# M900D.net
KiCad netlist of a schematic drawn in EAGLE
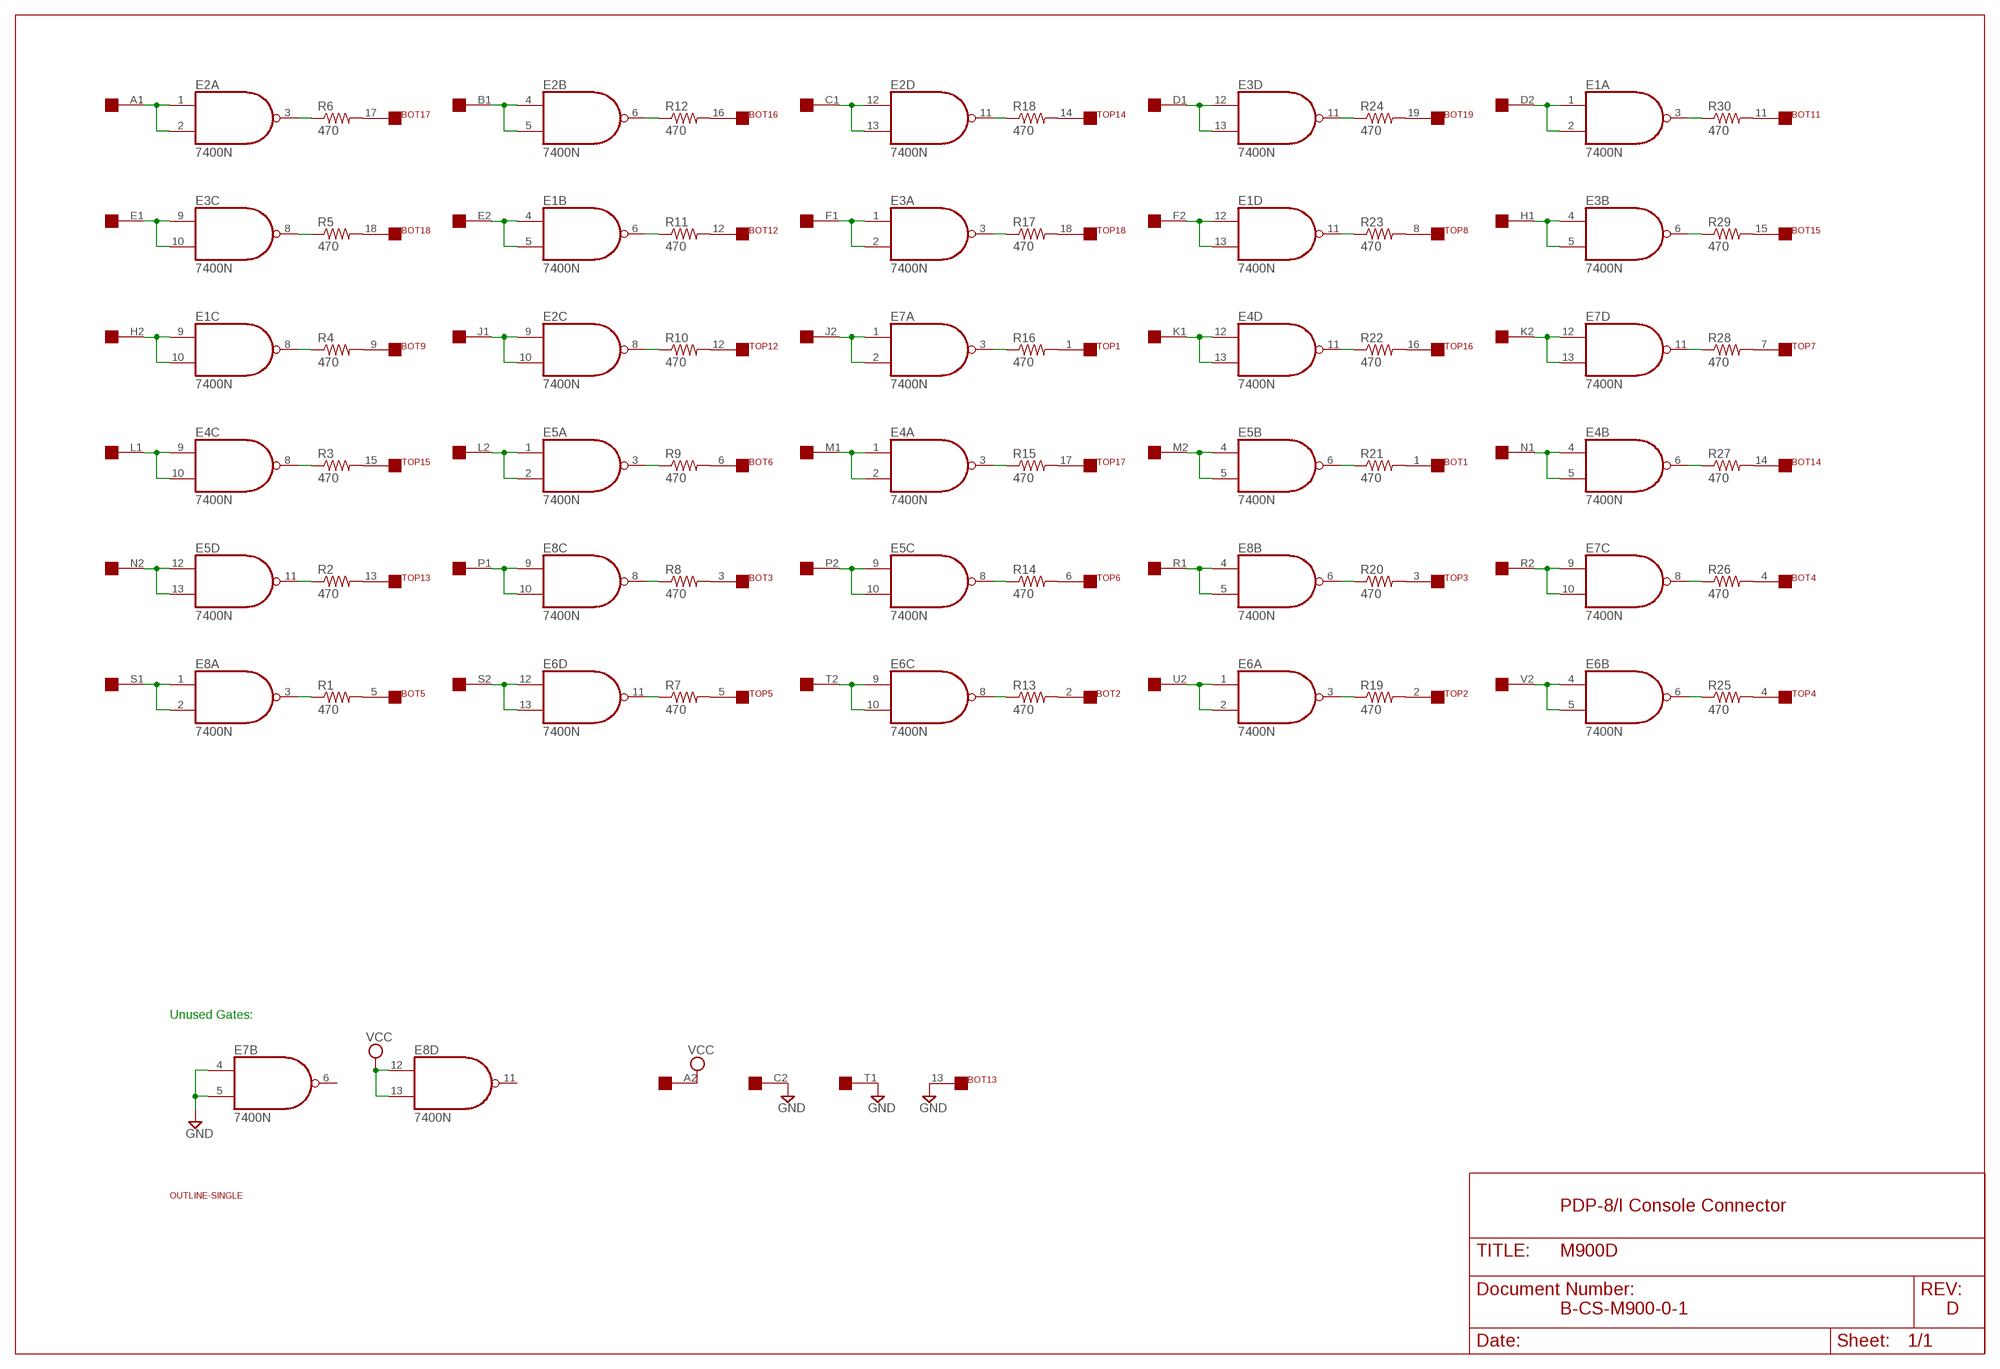
[diagram p0: schematic, sheet 1]

(export (version "E")
  (design (tool "Eeschema 10.0.6"))
  (components
    (comp (ref "BOT")
      (value "FLEX19")
      (footprint "eagle-import:FLEX19")
      (libsource (lib "eagle-import") (part "FLEX19"))
    )
    (comp (ref "E1")
      (value "7400N")
      (footprint "eagle-import:DIL14")
      (libsource (lib "eagle-import") (part "7400N"))
    )
    (comp (ref "E2")
      (value "7400N")
      (footprint "eagle-import:DIL14")
      (libsource (lib "eagle-import") (part "7400N"))
    )
    (comp (ref "E3")
      (value "7400N")
      (footprint "eagle-import:DIL14")
      (libsource (lib "eagle-import") (part "7400N"))
    )
    (comp (ref "E4")
      (value "7400N")
      (footprint "eagle-import:DIL14")
      (libsource (lib "eagle-import") (part "7400N"))
    )
    (comp (ref "E5")
      (value "7400N")
      (footprint "eagle-import:DIL14")
      (libsource (lib "eagle-import") (part "7400N"))
    )
    (comp (ref "E6")
      (value "7400N")
      (footprint "eagle-import:DIL14")
      (libsource (lib "eagle-import") (part "7400N"))
    )
    (comp (ref "E7")
      (value "7400N")
      (footprint "eagle-import:DIL14")
      (libsource (lib "eagle-import") (part "7400N"))
    )
    (comp (ref "E8")
      (value "7400N")
      (footprint "eagle-import:DIL14")
      (libsource (lib "eagle-import") (part "7400N"))
    )
    (comp (ref "EDGE")
      (value "SINGLE")
      (footprint "eagle-import:EDGE-CON2")
      (libsource (lib "eagle-import") (part "SINGLE"))
    )
    (comp (ref "R1")
      (value "470")
      (footprint "eagle-import:0207_10")
      (libsource (lib "eagle-import") (part "R-US_0207/10"))
    )
    (comp (ref "R2")
      (value "470")
      (footprint "eagle-import:0207_10")
      (libsource (lib "eagle-import") (part "R-US_0207/10"))
    )
    (comp (ref "R3")
      (value "470")
      (footprint "eagle-import:0207_10")
      (libsource (lib "eagle-import") (part "R-US_0207/10"))
    )
    (comp (ref "R4")
      (value "470")
      (footprint "eagle-import:0207_10")
      (libsource (lib "eagle-import") (part "R-US_0207/10"))
    )
    (comp (ref "R5")
      (value "470")
      (footprint "eagle-import:0207_10")
      (libsource (lib "eagle-import") (part "R-US_0207/10"))
    )
    (comp (ref "R6")
      (value "470")
      (footprint "eagle-import:0207_10")
      (libsource (lib "eagle-import") (part "R-US_0207/10"))
    )
    (comp (ref "R7")
      (value "470")
      (footprint "eagle-import:0207_10")
      (libsource (lib "eagle-import") (part "R-US_0207/10"))
    )
    (comp (ref "R8")
      (value "470")
      (footprint "eagle-import:0207_10")
      (libsource (lib "eagle-import") (part "R-US_0207/10"))
    )
    (comp (ref "R9")
      (value "470")
      (footprint "eagle-import:0207_10")
      (libsource (lib "eagle-import") (part "R-US_0207/10"))
    )
    (comp (ref "R10")
      (value "470")
      (footprint "eagle-import:0207_10")
      (libsource (lib "eagle-import") (part "R-US_0207/10"))
    )
    (comp (ref "R11")
      (value "470")
      (footprint "eagle-import:0207_10")
      (libsource (lib "eagle-import") (part "R-US_0207/10"))
    )
    (comp (ref "R12")
      (value "470")
      (footprint "eagle-import:0207_10")
      (libsource (lib "eagle-import") (part "R-US_0207/10"))
    )
    (comp (ref "R13")
      (value "470")
      (footprint "eagle-import:0207_10")
      (libsource (lib "eagle-import") (part "R-US_0207/10"))
    )
    (comp (ref "R14")
      (value "470")
      (footprint "eagle-import:0207_10")
      (libsource (lib "eagle-import") (part "R-US_0207/10"))
    )
    (comp (ref "R15")
      (value "470")
      (footprint "eagle-import:0207_10")
      (libsource (lib "eagle-import") (part "R-US_0207/10"))
    )
    (comp (ref "R16")
      (value "470")
      (footprint "eagle-import:0207_10")
      (libsource (lib "eagle-import") (part "R-US_0207/10"))
    )
    (comp (ref "R17")
      (value "470")
      (footprint "eagle-import:0207_10")
      (libsource (lib "eagle-import") (part "R-US_0207/10"))
    )
    (comp (ref "R18")
      (value "470")
      (footprint "eagle-import:0207_10")
      (libsource (lib "eagle-import") (part "R-US_0207/10"))
    )
    (comp (ref "R19")
      (value "470")
      (footprint "eagle-import:0207_10")
      (libsource (lib "eagle-import") (part "R-US_0207/10"))
    )
    (comp (ref "R20")
      (value "470")
      (footprint "eagle-import:0207_10")
      (libsource (lib "eagle-import") (part "R-US_0207/10"))
    )
    (comp (ref "R21")
      (value "470")
      (footprint "eagle-import:0207_10")
      (libsource (lib "eagle-import") (part "R-US_0207/10"))
    )
    (comp (ref "R22")
      (value "470")
      (footprint "eagle-import:0207_10")
      (libsource (lib "eagle-import") (part "R-US_0207/10"))
    )
    (comp (ref "R23")
      (value "470")
      (footprint "eagle-import:0207_10")
      (libsource (lib "eagle-import") (part "R-US_0207/10"))
    )
    (comp (ref "R24")
      (value "470")
      (footprint "eagle-import:0207_10")
      (libsource (lib "eagle-import") (part "R-US_0207/10"))
    )
    (comp (ref "R25")
      (value "470")
      (footprint "eagle-import:0207_10")
      (libsource (lib "eagle-import") (part "R-US_0207/10"))
    )
    (comp (ref "R26")
      (value "470")
      (footprint "eagle-import:0207_10")
      (libsource (lib "eagle-import") (part "R-US_0207/10"))
    )
    (comp (ref "R27")
      (value "470")
      (footprint "eagle-import:0207_10")
      (libsource (lib "eagle-import") (part "R-US_0207/10"))
    )
    (comp (ref "R28")
      (value "470")
      (footprint "eagle-import:0207_10")
      (libsource (lib "eagle-import") (part "R-US_0207/10"))
    )
    (comp (ref "R29")
      (value "470")
      (footprint "eagle-import:0207_10")
      (libsource (lib "eagle-import") (part "R-US_0207/10"))
    )
    (comp (ref "R30")
      (value "470")
      (footprint "eagle-import:0207_10")
      (libsource (lib "eagle-import") (part "R-US_0207/10"))
    )
    (comp (ref "TOP")
      (value "FLEX19")
      (footprint "eagle-import:FLEX19")
      (libsource (lib "eagle-import") (part "FLEX19"))
    )
    (comp (ref "U$2")
      (value "OUTLINE-SINGLE")
      (footprint "eagle-import:SINGLE")
      (libsource (lib "eagle-import") (part "OUTLINE-SINGLE"))
    )
  )
  (nets
    (net (code "1") (name "GND") (class "Default")
      (node (ref "BOT") (pin "13") (pinfunction "1_13") (pintype "passive"))
      (node (ref "E7") (pin "4") (pinfunction "I0_4") (pintype "input"))
      (node (ref "E7") (pin "5") (pinfunction "I1_5") (pintype "input"))
      (node (ref "EDGE") (pin "C2") (pinfunction "1_C2") (pintype "bidirectional"))
      (node (ref "EDGE") (pin "T1") (pinfunction "1_T1") (pintype "bidirectional"))
    )
    (net (code "2") (name "Net-(BOT-Pad1)") (class "Default")
      (node (ref "BOT") (pin "1") (pinfunction "1_1") (pintype "passive"))
      (node (ref "R21") (pin "2") (pinfunction "2_2") (pintype "passive"))
    )
    (net (code "3") (name "Net-(BOTC-1)") (class "Default")
      (node (ref "BOT") (pin "11") (pinfunction "1_11") (pintype "passive"))
      (node (ref "R30") (pin "2") (pinfunction "2_2") (pintype "passive"))
    )
    (net (code "4") (name "Net-(BOTD-1)") (class "Default")
      (node (ref "BOT") (pin "12") (pinfunction "1_12") (pintype "passive"))
      (node (ref "R11") (pin "2") (pinfunction "2_2") (pintype "passive"))
    )
    (net (code "5") (name "Net-(BOTF-1)") (class "Default")
      (node (ref "BOT") (pin "14") (pinfunction "1_14") (pintype "passive"))
      (node (ref "R27") (pin "2") (pinfunction "2_2") (pintype "passive"))
    )
    (net (code "6") (name "Net-(BOTG-1)") (class "Default")
      (node (ref "BOT") (pin "15") (pinfunction "1_15") (pintype "passive"))
      (node (ref "R29") (pin "2") (pinfunction "2_2") (pintype "passive"))
    )
    (net (code "7") (name "Net-(BOTH-1)") (class "Default")
      (node (ref "BOT") (pin "16") (pinfunction "1_16") (pintype "passive"))
      (node (ref "R12") (pin "2") (pinfunction "2_2") (pintype "passive"))
    )
    (net (code "8") (name "Net-(BOTI-1)") (class "Default")
      (node (ref "BOT") (pin "17") (pinfunction "1_17") (pintype "passive"))
      (node (ref "R6") (pin "2") (pinfunction "2_2") (pintype "passive"))
    )
    (net (code "9") (name "Net-(BOTJ-1)") (class "Default")
      (node (ref "BOT") (pin "18") (pinfunction "1_18") (pintype "passive"))
      (node (ref "R5") (pin "2") (pinfunction "2_2") (pintype "passive"))
    )
    (net (code "10") (name "Net-(BOTK-1)") (class "Default")
      (node (ref "BOT") (pin "19") (pinfunction "1_19") (pintype "passive"))
      (node (ref "R24") (pin "2") (pinfunction "2_2") (pintype "passive"))
    )
    (net (code "11") (name "Net-(BOTL-1)") (class "Default")
      (node (ref "BOT") (pin "2") (pinfunction "1_2") (pintype "passive"))
      (node (ref "R13") (pin "2") (pinfunction "2_2") (pintype "passive"))
    )
    (net (code "12") (name "Net-(BOTM-1)") (class "Default")
      (node (ref "BOT") (pin "3") (pinfunction "1_3") (pintype "passive"))
      (node (ref "R8") (pin "2") (pinfunction "2_2") (pintype "passive"))
    )
    (net (code "13") (name "Net-(BOTN-1)") (class "Default")
      (node (ref "BOT") (pin "4") (pinfunction "1_4") (pintype "passive"))
      (node (ref "R26") (pin "2") (pinfunction "2_2") (pintype "passive"))
    )
    (net (code "14") (name "Net-(BOTO-1)") (class "Default")
      (node (ref "BOT") (pin "5") (pinfunction "1_5") (pintype "passive"))
      (node (ref "R1") (pin "2") (pinfunction "2_2") (pintype "passive"))
    )
    (net (code "15") (name "Net-(BOTP-1)") (class "Default")
      (node (ref "BOT") (pin "6") (pinfunction "1_6") (pintype "passive"))
      (node (ref "R9") (pin "2") (pinfunction "2_2") (pintype "passive"))
    )
    (net (code "16") (name "Net-(BOTS-1)") (class "Default")
      (node (ref "BOT") (pin "9") (pinfunction "1_9") (pintype "passive"))
      (node (ref "R4") (pin "2") (pinfunction "2_2") (pintype "passive"))
    )
    (net (code "17") (name "Net-(E1A-I0)") (class "Default")
      (node (ref "E1") (pin "1") (pinfunction "I0_1") (pintype "input"))
      (node (ref "E1") (pin "2") (pinfunction "I1_2") (pintype "input"))
      (node (ref "EDGE") (pin "D2") (pinfunction "1_D2") (pintype "bidirectional"))
    )
    (net (code "18") (name "Net-(E1A-O)") (class "Default")
      (node (ref "E1") (pin "3") (pinfunction "O_3") (pintype "output"))
      (node (ref "R30") (pin "1") (pinfunction "1_1") (pintype "passive"))
    )
    (net (code "19") (name "Net-(E1B-I0)") (class "Default")
      (node (ref "E1") (pin "4") (pinfunction "I0_4") (pintype "input"))
      (node (ref "E1") (pin "5") (pinfunction "I1_5") (pintype "input"))
      (node (ref "EDGE") (pin "E2") (pinfunction "1_E2") (pintype "bidirectional"))
    )
    (net (code "20") (name "Net-(E1B-O)") (class "Default")
      (node (ref "E1") (pin "6") (pinfunction "O_6") (pintype "output"))
      (node (ref "R11") (pin "1") (pinfunction "1_1") (pintype "passive"))
    )
    (net (code "21") (name "Net-(E1C-I0)") (class "Default")
      (node (ref "E1") (pin "10") (pinfunction "I1_10") (pintype "input"))
      (node (ref "E1") (pin "9") (pinfunction "I0_9") (pintype "input"))
      (node (ref "EDGE") (pin "H2") (pinfunction "1_H2") (pintype "bidirectional"))
    )
    (net (code "22") (name "Net-(E1C-O)") (class "Default")
      (node (ref "E1") (pin "8") (pinfunction "O_8") (pintype "output"))
      (node (ref "R4") (pin "1") (pinfunction "1_1") (pintype "passive"))
    )
    (net (code "23") (name "Net-(E1D-I0)") (class "Default")
      (node (ref "E1") (pin "12") (pinfunction "I0_12") (pintype "input"))
      (node (ref "E1") (pin "13") (pinfunction "I1_13") (pintype "input"))
      (node (ref "EDGE") (pin "F2") (pinfunction "1_F2") (pintype "bidirectional"))
    )
    (net (code "24") (name "Net-(E1D-O)") (class "Default")
      (node (ref "E1") (pin "11") (pinfunction "O_11") (pintype "output"))
      (node (ref "R23") (pin "1") (pinfunction "1_1") (pintype "passive"))
    )
    (net (code "25") (name "Net-(E2A-I0)") (class "Default")
      (node (ref "E2") (pin "1") (pinfunction "I0_1") (pintype "input"))
      (node (ref "E2") (pin "2") (pinfunction "I1_2") (pintype "input"))
      (node (ref "EDGE") (pin "A1") (pinfunction "1_A1") (pintype "bidirectional"))
    )
    (net (code "26") (name "Net-(E2A-O)") (class "Default")
      (node (ref "E2") (pin "3") (pinfunction "O_3") (pintype "output"))
      (node (ref "R6") (pin "1") (pinfunction "1_1") (pintype "passive"))
    )
    (net (code "27") (name "Net-(E2B-I0)") (class "Default")
      (node (ref "E2") (pin "4") (pinfunction "I0_4") (pintype "input"))
      (node (ref "E2") (pin "5") (pinfunction "I1_5") (pintype "input"))
      (node (ref "EDGE") (pin "B1") (pinfunction "1_B1") (pintype "bidirectional"))
    )
    (net (code "28") (name "Net-(E2B-O)") (class "Default")
      (node (ref "E2") (pin "6") (pinfunction "O_6") (pintype "output"))
      (node (ref "R12") (pin "1") (pinfunction "1_1") (pintype "passive"))
    )
    (net (code "29") (name "Net-(E2C-I0)") (class "Default")
      (node (ref "E2") (pin "10") (pinfunction "I1_10") (pintype "input"))
      (node (ref "E2") (pin "9") (pinfunction "I0_9") (pintype "input"))
      (node (ref "EDGE") (pin "J1") (pinfunction "1_J1") (pintype "bidirectional"))
    )
    (net (code "30") (name "Net-(E2C-O)") (class "Default")
      (node (ref "E2") (pin "8") (pinfunction "O_8") (pintype "output"))
      (node (ref "R10") (pin "1") (pinfunction "1_1") (pintype "passive"))
    )
    (net (code "31") (name "Net-(E2D-I0)") (class "Default")
      (node (ref "E2") (pin "12") (pinfunction "I0_12") (pintype "input"))
      (node (ref "E2") (pin "13") (pinfunction "I1_13") (pintype "input"))
      (node (ref "EDGE") (pin "C1") (pinfunction "1_C1") (pintype "bidirectional"))
    )
    (net (code "32") (name "Net-(E2D-O)") (class "Default")
      (node (ref "E2") (pin "11") (pinfunction "O_11") (pintype "output"))
      (node (ref "R18") (pin "1") (pinfunction "1_1") (pintype "passive"))
    )
    (net (code "33") (name "Net-(E3A-I0)") (class "Default")
      (node (ref "E3") (pin "1") (pinfunction "I0_1") (pintype "input"))
      (node (ref "E3") (pin "2") (pinfunction "I1_2") (pintype "input"))
      (node (ref "EDGE") (pin "F1") (pinfunction "1_F1") (pintype "bidirectional"))
    )
    (net (code "34") (name "Net-(E3A-O)") (class "Default")
      (node (ref "E3") (pin "3") (pinfunction "O_3") (pintype "output"))
      (node (ref "R17") (pin "1") (pinfunction "1_1") (pintype "passive"))
    )
    (net (code "35") (name "Net-(E3B-I0)") (class "Default")
      (node (ref "E3") (pin "4") (pinfunction "I0_4") (pintype "input"))
      (node (ref "E3") (pin "5") (pinfunction "I1_5") (pintype "input"))
      (node (ref "EDGE") (pin "H1") (pinfunction "1_H1") (pintype "bidirectional"))
    )
    (net (code "36") (name "Net-(E3B-O)") (class "Default")
      (node (ref "E3") (pin "6") (pinfunction "O_6") (pintype "output"))
      (node (ref "R29") (pin "1") (pinfunction "1_1") (pintype "passive"))
    )
    (net (code "37") (name "Net-(E3C-I0)") (class "Default")
      (node (ref "E3") (pin "10") (pinfunction "I1_10") (pintype "input"))
      (node (ref "E3") (pin "9") (pinfunction "I0_9") (pintype "input"))
      (node (ref "EDGE") (pin "E1") (pinfunction "1_E1") (pintype "bidirectional"))
    )
    (net (code "38") (name "Net-(E3C-O)") (class "Default")
      (node (ref "E3") (pin "8") (pinfunction "O_8") (pintype "output"))
      (node (ref "R5") (pin "1") (pinfunction "1_1") (pintype "passive"))
    )
    (net (code "39") (name "Net-(E3D-I0)") (class "Default")
      (node (ref "E3") (pin "12") (pinfunction "I0_12") (pintype "input"))
      (node (ref "E3") (pin "13") (pinfunction "I1_13") (pintype "input"))
      (node (ref "EDGE") (pin "D1") (pinfunction "1_D1") (pintype "bidirectional"))
    )
    (net (code "40") (name "Net-(E3D-O)") (class "Default")
      (node (ref "E3") (pin "11") (pinfunction "O_11") (pintype "output"))
      (node (ref "R24") (pin "1") (pinfunction "1_1") (pintype "passive"))
    )
    (net (code "41") (name "Net-(E4A-I0)") (class "Default")
      (node (ref "E4") (pin "1") (pinfunction "I0_1") (pintype "input"))
      (node (ref "E4") (pin "2") (pinfunction "I1_2") (pintype "input"))
      (node (ref "EDGE") (pin "M1") (pinfunction "1_M1") (pintype "bidirectional"))
    )
    (net (code "42") (name "Net-(E4A-O)") (class "Default")
      (node (ref "E4") (pin "3") (pinfunction "O_3") (pintype "output"))
      (node (ref "R15") (pin "1") (pinfunction "1_1") (pintype "passive"))
    )
    (net (code "43") (name "Net-(E4B-I0)") (class "Default")
      (node (ref "E4") (pin "4") (pinfunction "I0_4") (pintype "input"))
      (node (ref "E4") (pin "5") (pinfunction "I1_5") (pintype "input"))
      (node (ref "EDGE") (pin "N1") (pinfunction "1_N1") (pintype "bidirectional"))
    )
    (net (code "44") (name "Net-(E4B-O)") (class "Default")
      (node (ref "E4") (pin "6") (pinfunction "O_6") (pintype "output"))
      (node (ref "R27") (pin "1") (pinfunction "1_1") (pintype "passive"))
    )
    (net (code "45") (name "Net-(E4C-I0)") (class "Default")
      (node (ref "E4") (pin "10") (pinfunction "I1_10") (pintype "input"))
      (node (ref "E4") (pin "9") (pinfunction "I0_9") (pintype "input"))
      (node (ref "EDGE") (pin "L1") (pinfunction "1_L1") (pintype "bidirectional"))
    )
    (net (code "46") (name "Net-(E4C-O)") (class "Default")
      (node (ref "E4") (pin "8") (pinfunction "O_8") (pintype "output"))
      (node (ref "R3") (pin "1") (pinfunction "1_1") (pintype "passive"))
    )
    (net (code "47") (name "Net-(E4D-I0)") (class "Default")
      (node (ref "E4") (pin "12") (pinfunction "I0_12") (pintype "input"))
      (node (ref "E4") (pin "13") (pinfunction "I1_13") (pintype "input"))
      (node (ref "EDGE") (pin "K1") (pinfunction "1_K1") (pintype "bidirectional"))
    )
    (net (code "48") (name "Net-(E4D-O)") (class "Default")
      (node (ref "E4") (pin "11") (pinfunction "O_11") (pintype "output"))
      (node (ref "R22") (pin "1") (pinfunction "1_1") (pintype "passive"))
    )
    (net (code "49") (name "Net-(E5A-I0)") (class "Default")
      (node (ref "E5") (pin "1") (pinfunction "I0_1") (pintype "input"))
      (node (ref "E5") (pin "2") (pinfunction "I1_2") (pintype "input"))
      (node (ref "EDGE") (pin "L2") (pinfunction "1_L2") (pintype "bidirectional"))
    )
    (net (code "50") (name "Net-(E5A-O)") (class "Default")
      (node (ref "E5") (pin "3") (pinfunction "O_3") (pintype "output"))
      (node (ref "R9") (pin "1") (pinfunction "1_1") (pintype "passive"))
    )
    (net (code "51") (name "Net-(E5B-I0)") (class "Default")
      (node (ref "E5") (pin "4") (pinfunction "I0_4") (pintype "input"))
      (node (ref "E5") (pin "5") (pinfunction "I1_5") (pintype "input"))
      (node (ref "EDGE") (pin "M2") (pinfunction "1_M2") (pintype "bidirectional"))
    )
    (net (code "52") (name "Net-(E5B-O)") (class "Default")
      (node (ref "E5") (pin "6") (pinfunction "O_6") (pintype "output"))
      (node (ref "R21") (pin "1") (pinfunction "1_1") (pintype "passive"))
    )
    (net (code "53") (name "Net-(E5C-I0)") (class "Default")
      (node (ref "E5") (pin "10") (pinfunction "I1_10") (pintype "input"))
      (node (ref "E5") (pin "9") (pinfunction "I0_9") (pintype "input"))
      (node (ref "EDGE") (pin "P2") (pinfunction "1_P2") (pintype "bidirectional"))
    )
    (net (code "54") (name "Net-(E5C-O)") (class "Default")
      (node (ref "E5") (pin "8") (pinfunction "O_8") (pintype "output"))
      (node (ref "R14") (pin "1") (pinfunction "1_1") (pintype "passive"))
    )
    (net (code "55") (name "Net-(E5D-I0)") (class "Default")
      (node (ref "E5") (pin "12") (pinfunction "I0_12") (pintype "input"))
      (node (ref "E5") (pin "13") (pinfunction "I1_13") (pintype "input"))
      (node (ref "EDGE") (pin "N2") (pinfunction "1_N2") (pintype "bidirectional"))
    )
    (net (code "56") (name "Net-(E5D-O)") (class "Default")
      (node (ref "E5") (pin "11") (pinfunction "O_11") (pintype "output"))
      (node (ref "R2") (pin "1") (pinfunction "1_1") (pintype "passive"))
    )
    (net (code "57") (name "Net-(E6A-I0)") (class "Default")
      (node (ref "E6") (pin "1") (pinfunction "I0_1") (pintype "input"))
      (node (ref "E6") (pin "2") (pinfunction "I1_2") (pintype "input"))
      (node (ref "EDGE") (pin "U2") (pinfunction "1_U2") (pintype "bidirectional"))
    )
    (net (code "58") (name "Net-(E6A-O)") (class "Default")
      (node (ref "E6") (pin "3") (pinfunction "O_3") (pintype "output"))
      (node (ref "R19") (pin "1") (pinfunction "1_1") (pintype "passive"))
    )
    (net (code "59") (name "Net-(E6B-I0)") (class "Default")
      (node (ref "E6") (pin "4") (pinfunction "I0_4") (pintype "input"))
      (node (ref "E6") (pin "5") (pinfunction "I1_5") (pintype "input"))
      (node (ref "EDGE") (pin "V2") (pinfunction "1_V2") (pintype "bidirectional"))
    )
    (net (code "60") (name "Net-(E6B-O)") (class "Default")
      (node (ref "E6") (pin "6") (pinfunction "O_6") (pintype "output"))
      (node (ref "R25") (pin "1") (pinfunction "1_1") (pintype "passive"))
    )
    (net (code "61") (name "Net-(E6C-I0)") (class "Default")
      (node (ref "E6") (pin "10") (pinfunction "I1_10") (pintype "input"))
      (node (ref "E6") (pin "9") (pinfunction "I0_9") (pintype "input"))
      (node (ref "EDGE") (pin "T2") (pinfunction "1_T2") (pintype "bidirectional"))
    )
    (net (code "62") (name "Net-(E6C-O)") (class "Default")
      (node (ref "E6") (pin "8") (pinfunction "O_8") (pintype "output"))
      (node (ref "R13") (pin "1") (pinfunction "1_1") (pintype "passive"))
    )
    (net (code "63") (name "Net-(E6D-I0)") (class "Default")
      (node (ref "E6") (pin "12") (pinfunction "I0_12") (pintype "input"))
      (node (ref "E6") (pin "13") (pinfunction "I1_13") (pintype "input"))
      (node (ref "EDGE") (pin "S2") (pinfunction "1_S2") (pintype "bidirectional"))
    )
    (net (code "64") (name "Net-(E6D-O)") (class "Default")
      (node (ref "E6") (pin "11") (pinfunction "O_11") (pintype "output"))
      (node (ref "R7") (pin "1") (pinfunction "1_1") (pintype "passive"))
    )
    (net (code "65") (name "Net-(E7A-I0)") (class "Default")
      (node (ref "E7") (pin "1") (pinfunction "I0_1") (pintype "input"))
      (node (ref "E7") (pin "2") (pinfunction "I1_2") (pintype "input"))
      (node (ref "EDGE") (pin "J2") (pinfunction "1_J2") (pintype "bidirectional"))
    )
    (net (code "66") (name "Net-(E7A-O)") (class "Default")
      (node (ref "E7") (pin "3") (pinfunction "O_3") (pintype "output"))
      (node (ref "R16") (pin "1") (pinfunction "1_1") (pintype "passive"))
    )
    (net (code "67") (name "Net-(E7C-I0)") (class "Default")
      (node (ref "E7") (pin "10") (pinfunction "I1_10") (pintype "input"))
      (node (ref "E7") (pin "9") (pinfunction "I0_9") (pintype "input"))
      (node (ref "EDGE") (pin "R2") (pinfunction "1_R2") (pintype "bidirectional"))
    )
    (net (code "68") (name "Net-(E7C-O)") (class "Default")
      (node (ref "E7") (pin "8") (pinfunction "O_8") (pintype "output"))
      (node (ref "R26") (pin "1") (pinfunction "1_1") (pintype "passive"))
    )
    (net (code "69") (name "Net-(E7D-I0)") (class "Default")
      (node (ref "E7") (pin "12") (pinfunction "I0_12") (pintype "input"))
      (node (ref "E7") (pin "13") (pinfunction "I1_13") (pintype "input"))
      (node (ref "EDGE") (pin "K2") (pinfunction "1_K2") (pintype "bidirectional"))
    )
    (net (code "70") (name "Net-(E7D-O)") (class "Default")
      (node (ref "E7") (pin "11") (pinfunction "O_11") (pintype "output"))
      (node (ref "R28") (pin "1") (pinfunction "1_1") (pintype "passive"))
    )
    (net (code "71") (name "Net-(E8A-I0)") (class "Default")
      (node (ref "E8") (pin "1") (pinfunction "I0_1") (pintype "input"))
      (node (ref "E8") (pin "2") (pinfunction "I1_2") (pintype "input"))
      (node (ref "EDGE") (pin "S1") (pinfunction "1_S1") (pintype "bidirectional"))
    )
    (net (code "72") (name "Net-(E8A-O)") (class "Default")
      (node (ref "E8") (pin "3") (pinfunction "O_3") (pintype "output"))
      (node (ref "R1") (pin "1") (pinfunction "1_1") (pintype "passive"))
    )
    (net (code "73") (name "Net-(E8B-I0)") (class "Default")
      (node (ref "E8") (pin "4") (pinfunction "I0_4") (pintype "input"))
      (node (ref "E8") (pin "5") (pinfunction "I1_5") (pintype "input"))
      (node (ref "EDGE") (pin "R1") (pinfunction "1_R1") (pintype "bidirectional"))
    )
    (net (code "74") (name "Net-(E8B-O)") (class "Default")
      (node (ref "E8") (pin "6") (pinfunction "O_6") (pintype "output"))
      (node (ref "R20") (pin "1") (pinfunction "1_1") (pintype "passive"))
    )
    (net (code "75") (name "Net-(E8C-I0)") (class "Default")
      (node (ref "E8") (pin "10") (pinfunction "I1_10") (pintype "input"))
      (node (ref "E8") (pin "9") (pinfunction "I0_9") (pintype "input"))
      (node (ref "EDGE") (pin "P1") (pinfunction "1_P1") (pintype "bidirectional"))
    )
    (net (code "76") (name "Net-(E8C-O)") (class "Default")
      (node (ref "E8") (pin "8") (pinfunction "O_8") (pintype "output"))
      (node (ref "R8") (pin "1") (pinfunction "1_1") (pintype "passive"))
    )
    (net (code "77") (name "Net-(R16-Pad2)") (class "Default")
      (node (ref "R16") (pin "2") (pinfunction "2_2") (pintype "passive"))
      (node (ref "TOP") (pin "1") (pinfunction "1_1") (pintype "passive"))
    )
    (net (code "78") (name "Net-(TOPD-1)") (class "Default")
      (node (ref "R10") (pin "2") (pinfunction "2_2") (pintype "passive"))
      (node (ref "TOP") (pin "12") (pinfunction "1_12") (pintype "passive"))
    )
    (net (code "79") (name "Net-(TOPE-1)") (class "Default")
      (node (ref "R2") (pin "2") (pinfunction "2_2") (pintype "passive"))
      (node (ref "TOP") (pin "13") (pinfunction "1_13") (pintype "passive"))
    )
    (net (code "80") (name "Net-(TOPF-1)") (class "Default")
      (node (ref "R18") (pin "2") (pinfunction "2_2") (pintype "passive"))
      (node (ref "TOP") (pin "14") (pinfunction "1_14") (pintype "passive"))
    )
    (net (code "81") (name "Net-(TOPG-1)") (class "Default")
      (node (ref "R3") (pin "2") (pinfunction "2_2") (pintype "passive"))
      (node (ref "TOP") (pin "15") (pinfunction "1_15") (pintype "passive"))
    )
    (net (code "82") (name "Net-(TOPH-1)") (class "Default")
      (node (ref "R22") (pin "2") (pinfunction "2_2") (pintype "passive"))
      (node (ref "TOP") (pin "16") (pinfunction "1_16") (pintype "passive"))
    )
    (net (code "83") (name "Net-(TOPI-1)") (class "Default")
      (node (ref "R15") (pin "2") (pinfunction "2_2") (pintype "passive"))
      (node (ref "TOP") (pin "17") (pinfunction "1_17") (pintype "passive"))
    )
    (net (code "84") (name "Net-(TOPJ-1)") (class "Default")
      (node (ref "R17") (pin "2") (pinfunction "2_2") (pintype "passive"))
      (node (ref "TOP") (pin "18") (pinfunction "1_18") (pintype "passive"))
    )
    (net (code "85") (name "Net-(TOPL-1)") (class "Default")
      (node (ref "R19") (pin "2") (pinfunction "2_2") (pintype "passive"))
      (node (ref "TOP") (pin "2") (pinfunction "1_2") (pintype "passive"))
    )
    (net (code "86") (name "Net-(TOPM-1)") (class "Default")
      (node (ref "R20") (pin "2") (pinfunction "2_2") (pintype "passive"))
      (node (ref "TOP") (pin "3") (pinfunction "1_3") (pintype "passive"))
    )
    (net (code "87") (name "Net-(TOPN-1)") (class "Default")
      (node (ref "R25") (pin "2") (pinfunction "2_2") (pintype "passive"))
      (node (ref "TOP") (pin "4") (pinfunction "1_4") (pintype "passive"))
    )
    (net (code "88") (name "Net-(TOPO-1)") (class "Default")
      (node (ref "R7") (pin "2") (pinfunction "2_2") (pintype "passive"))
      (node (ref "TOP") (pin "5") (pinfunction "1_5") (pintype "passive"))
    )
    (net (code "89") (name "Net-(TOPP-1)") (class "Default")
      (node (ref "R14") (pin "2") (pinfunction "2_2") (pintype "passive"))
      (node (ref "TOP") (pin "6") (pinfunction "1_6") (pintype "passive"))
    )
    (net (code "90") (name "Net-(TOPQ-1)") (class "Default")
      (node (ref "R28") (pin "2") (pinfunction "2_2") (pintype "passive"))
      (node (ref "TOP") (pin "7") (pinfunction "1_7") (pintype "passive"))
    )
    (net (code "91") (name "Net-(TOPR-1)") (class "Default")
      (node (ref "R23") (pin "2") (pinfunction "2_2") (pintype "passive"))
      (node (ref "TOP") (pin "8") (pinfunction "1_8") (pintype "passive"))
    )
    (net (code "92") (name "VCC") (class "Default")
      (node (ref "E8") (pin "12") (pinfunction "I0_12") (pintype "input"))
      (node (ref "E8") (pin "13") (pinfunction "I1_13") (pintype "input"))
      (node (ref "EDGE") (pin "A2") (pinfunction "1_A2") (pintype "bidirectional"))
    )
    (net (code "93") (name "unconnected-(E7B-O-Pad6)") (class "Default")
      (node (ref "E7") (pin "6") (pinfunction "O_6") (pintype "output"))
    )
    (net (code "94") (name "unconnected-(E8D-O-Pad11)") (class "Default")
      (node (ref "E8") (pin "11") (pinfunction "O_11") (pintype "output"))
    )
  )
)
